# WIFI_0831.net
KiCad netlist of a schematic drawn in Altium Designer
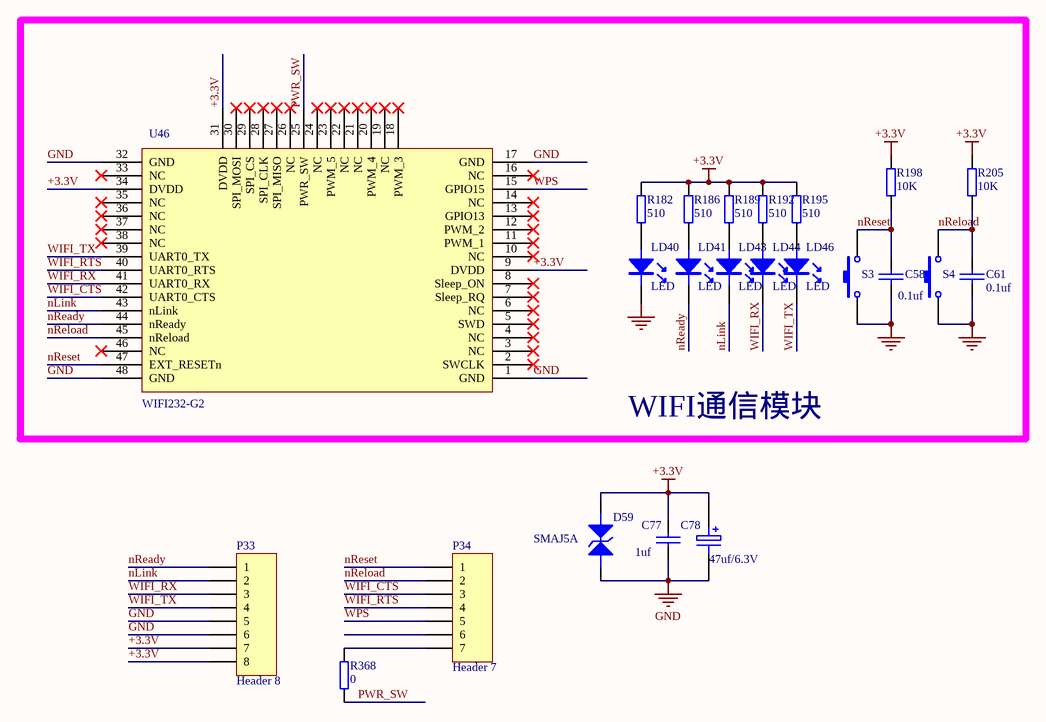
[diagram p0: 如意硬件WIFI模块0831.SchDoc]

(export (version "E")
  (design (tool "Eeschema 10.0.6"))
  (components
    (comp (ref "C58")
      (value "0.1uf")
      (footprint "0603C-1")
      (description "Capacitor")
      (libsource (lib "*") (part "CAP"))
    )
    (comp (ref "C61")
      (value "0.1uf")
      (footprint "0603C-1")
      (description "Capacitor")
      (libsource (lib "*") (part "CAP"))
    )
    (comp (ref "C77")
      (value "1uf")
      (footprint "0603C-1")
      (description "Capacitor")
      (libsource (lib "*") (part "CAP"))
    )
    (comp (ref "C78")
      (value "47uf/6.3V")
      (footprint "1206D-S")
      (description "Electrolytic Capacitor")
      (libsource (lib "*") (part "ELECTRO1"))
    )
    (comp (ref "D59") (value "SMAJ5A") (footprint "SMB") (libsource (lib "*") (part "TVS")))
    (comp (ref "LD40") (value "LED") (footprint "LED_Z1") (libsource (lib "*") (part "LED")))
    (comp (ref "LD41") (value "LED") (footprint "LED_Z1") (libsource (lib "*") (part "LED")))
    (comp (ref "LD43") (value "LED") (footprint "LED_Z1") (libsource (lib "*") (part "LED")))
    (comp (ref "LD44") (value "LED") (footprint "LED_Z1") (libsource (lib "*") (part "LED")))
    (comp (ref "LD46") (value "LED") (footprint "LED_Z1") (libsource (lib "*") (part "LED")))
    (comp (ref "P33")
      (value "Header 8")
      (footprint "HDR1X8")
      (description "Header, 8-Pin")
      (fields (field (name "PUBLISHER") "Altium Limited"))
      (libsource (lib "Miscellaneous Connectors") (part "Header 8"))
    )
    (comp (ref "P34")
      (value "Header 7")
      (footprint "HDR1X7")
      (description "Header, 7-Pin")
      (fields (field (name "PUBLISHER") "Altium Limited"))
      (libsource (lib "Miscellaneous Connectors") (part "Header 7"))
    )
    (comp (ref "R182") (value "510") (footprint "0603R-1") (libsource (lib "*") (part "RES-2")))
    (comp (ref "R186") (value "510") (footprint "0603R-1") (libsource (lib "*") (part "RES-2")))
    (comp (ref "R189") (value "510") (footprint "0603R-1") (libsource (lib "*") (part "RES-2")))
    (comp (ref "R192") (value "510") (footprint "0603R-1") (libsource (lib "*") (part "RES-2")))
    (comp (ref "R195") (value "510") (footprint "0603R-1") (libsource (lib "*") (part "RES-2")))
    (comp (ref "R198") (value "10K") (footprint "0603R-1") (libsource (lib "*") (part "RES-2")))
    (comp (ref "R205") (value "10K") (footprint "0603R-1") (libsource (lib "*") (part "RES-2")))
    (comp (ref "R368") (value "0") (footprint "0603R-1") (libsource (lib "*") (part "RES-2")))
    (comp (ref "S3")
      (value "SW-PB")
      (footprint "SW_PB4_A1")
      (description "Switch")
      (fields (field (name "PUBLISHER") "Altium Limited"))
      (libsource (lib "*") (part "SW-PB"))
    )
    (comp (ref "S4")
      (value "SW-PB")
      (footprint "SW_PB4_A1")
      (description "Switch")
      (fields (field (name "PUBLISHER") "Altium Limited"))
      (libsource (lib "*") (part "SW-PB"))
    )
    (comp (ref "U46")
      (value "WIFI232-G2")
      (footprint "USR-WIFI232-G2")
      (libsource (lib "zongruyi") (part "WIFI232-G2"))
    )
  )
  (nets
    (net (code "1") (name "+3.3V") (class "Default")
      (node (ref "C77") (pin "1") (pinfunction "1_1") (pintype "passive"))
      (node (ref "C78") (pin "1") (pinfunction "1_1") (pintype "passive"))
      (node (ref "D59") (pin "2") (pinfunction "K_2") (pintype "passive"))
      (node (ref "P33") (pin "7") (pinfunction "7_7") (pintype "passive"))
      (node (ref "P33") (pin "8") (pinfunction "8_8") (pintype "passive"))
      (node (ref "R182") (pin "1") (pinfunction "1_1") (pintype "passive"))
      (node (ref "R186") (pin "1") (pinfunction "1_1") (pintype "passive"))
      (node (ref "R189") (pin "1") (pinfunction "1_1") (pintype "passive"))
      (node (ref "R192") (pin "1") (pinfunction "1_1") (pintype "passive"))
      (node (ref "R195") (pin "1") (pinfunction "1_1") (pintype "passive"))
      (node (ref "R198") (pin "1") (pinfunction "1_1") (pintype "passive"))
      (node (ref "R205") (pin "1") (pinfunction "1_1") (pintype "passive"))
      (node (ref "U46") (pin "31") (pinfunction "DVDD_31") (pintype "passive"))
      (node (ref "U46") (pin "34") (pinfunction "DVDD_34") (pintype "passive"))
      (node (ref "U46") (pin "9") (pinfunction "DVDD_9") (pintype "passive"))
    )
    (net (code "2") (name "/PWR_SW") (class "Default")
      (node (ref "R368") (pin "2") (pinfunction "2_2") (pintype "passive"))
      (node (ref "U46") (pin "25") (pinfunction "PWR_SW_25") (pintype "passive"))
    )
    (net (code "3") (name "/WIFI_CTS") (class "Default")
      (node (ref "P34") (pin "3") (pinfunction "3_3") (pintype "passive"))
      (node (ref "U46") (pin "42") (pinfunction "UART0_CTS_42") (pintype "passive"))
    )
    (net (code "4") (name "/WIFI_RTS") (class "Default")
      (node (ref "P34") (pin "4") (pinfunction "4_4") (pintype "passive"))
      (node (ref "U46") (pin "40") (pinfunction "UART0_RTS_40") (pintype "passive"))
    )
    (net (code "5") (name "/WIFI_RX") (class "Default")
      (node (ref "LD44") (pin "2") (pinfunction "2_2") (pintype "passive"))
      (node (ref "P33") (pin "3") (pinfunction "3_3") (pintype "passive"))
      (node (ref "U46") (pin "41") (pinfunction "UART0_RX_41") (pintype "passive"))
    )
    (net (code "6") (name "/WIFI_TX") (class "Default")
      (node (ref "LD46") (pin "2") (pinfunction "2_2") (pintype "passive"))
      (node (ref "P33") (pin "4") (pinfunction "4_4") (pintype "passive"))
      (node (ref "U46") (pin "39") (pinfunction "UART0_TX_39") (pintype "passive"))
    )
    (net (code "7") (name "/WPS") (class "Default")
      (node (ref "P34") (pin "5") (pinfunction "5_5") (pintype "passive"))
      (node (ref "U46") (pin "15") (pinfunction "GPIO15_15") (pintype "passive"))
    )
    (net (code "8") (name "/nLink") (class "Default")
      (node (ref "LD43") (pin "2") (pinfunction "2_2") (pintype "passive"))
      (node (ref "P33") (pin "2") (pinfunction "2_2") (pintype "passive"))
      (node (ref "U46") (pin "43") (pinfunction "nLink_43") (pintype "passive"))
    )
    (net (code "9") (name "/nReady") (class "Default")
      (node (ref "LD41") (pin "2") (pinfunction "2_2") (pintype "passive"))
      (node (ref "P33") (pin "1") (pinfunction "1_1") (pintype "passive"))
      (node (ref "U46") (pin "44") (pinfunction "nReady_44") (pintype "passive"))
    )
    (net (code "10") (name "/nReload") (class "Default")
      (node (ref "C61") (pin "1") (pinfunction "1_1") (pintype "passive"))
      (node (ref "P34") (pin "2") (pinfunction "2_2") (pintype "passive"))
      (node (ref "R205") (pin "2") (pinfunction "2_2") (pintype "passive"))
      (node (ref "S4") (pin "2") (pinfunction "2_2") (pintype "passive"))
      (node (ref "U46") (pin "45") (pinfunction "nReload_45") (pintype "passive"))
    )
    (net (code "11") (name "/nReset") (class "Default")
      (node (ref "C58") (pin "1") (pinfunction "1_1") (pintype "passive"))
      (node (ref "P34") (pin "1") (pinfunction "1_1") (pintype "passive"))
      (node (ref "R198") (pin "2") (pinfunction "2_2") (pintype "passive"))
      (node (ref "S3") (pin "2") (pinfunction "2_2") (pintype "passive"))
      (node (ref "U46") (pin "47") (pinfunction "EXT_RESETn_47") (pintype "passive"))
    )
    (net (code "12") (name "GND") (class "Default")
      (node (ref "C58") (pin "2") (pinfunction "2_2") (pintype "passive"))
      (node (ref "C61") (pin "2") (pinfunction "2_2") (pintype "passive"))
      (node (ref "C77") (pin "2") (pinfunction "2_2") (pintype "passive"))
      (node (ref "C78") (pin "2") (pinfunction "2_2") (pintype "passive"))
      (node (ref "D59") (pin "1") (pinfunction "A_1") (pintype "passive"))
      (node (ref "LD40") (pin "2") (pinfunction "2_2") (pintype "passive"))
      (node (ref "P33") (pin "5") (pinfunction "5_5") (pintype "passive"))
      (node (ref "P33") (pin "6") (pinfunction "6_6") (pintype "passive"))
      (node (ref "S3") (pin "1") (pinfunction "1_1") (pintype "passive"))
      (node (ref "S4") (pin "1") (pinfunction "1_1") (pintype "passive"))
      (node (ref "U46") (pin "1") (pinfunction "GND_1") (pintype "passive"))
      (node (ref "U46") (pin "17") (pinfunction "GND_17") (pintype "passive"))
      (node (ref "U46") (pin "32") (pinfunction "GND_32") (pintype "passive"))
      (node (ref "U46") (pin "48") (pinfunction "GND_48") (pintype "passive"))
    )
    (net (code "13") (name "Net-(LD40-Pad1)") (class "Default")
      (node (ref "LD40") (pin "1") (pinfunction "1_1") (pintype "passive"))
      (node (ref "R182") (pin "2") (pinfunction "2_2") (pintype "passive"))
    )
    (net (code "14") (name "Net-(LD41-Pad1)") (class "Default")
      (node (ref "LD41") (pin "1") (pinfunction "1_1") (pintype "passive"))
      (node (ref "R186") (pin "2") (pinfunction "2_2") (pintype "passive"))
    )
    (net (code "15") (name "Net-(LD43-Pad1)") (class "Default")
      (node (ref "LD43") (pin "1") (pinfunction "1_1") (pintype "passive"))
      (node (ref "R189") (pin "2") (pinfunction "2_2") (pintype "passive"))
    )
    (net (code "16") (name "Net-(LD44-Pad1)") (class "Default")
      (node (ref "LD44") (pin "1") (pinfunction "1_1") (pintype "passive"))
      (node (ref "R192") (pin "2") (pinfunction "2_2") (pintype "passive"))
    )
    (net (code "17") (name "Net-(LD46-Pad1)") (class "Default")
      (node (ref "LD46") (pin "1") (pinfunction "1_1") (pintype "passive"))
      (node (ref "R195") (pin "2") (pinfunction "2_2") (pintype "passive"))
    )
    (net (code "18") (name "Net-(P34-Pad7)") (class "Default")
      (node (ref "P34") (pin "7") (pinfunction "7_7") (pintype "passive"))
      (node (ref "R368") (pin "1") (pinfunction "1_1") (pintype "passive"))
    )
    (net (code "19") (name "unconnected-(P34-Pad6)") (class "Default")
      (node (ref "P34") (pin "6") (pinfunction "6_6") (pintype "passive"))
    )
    (net (code "20") (name "unconnected-(U46-GPIO13-Pad13)") (class "Default")
      (node (ref "U46") (pin "13") (pinfunction "GPIO13_13") (pintype "passive+no_connect"))
    )
    (net (code "21") (name "unconnected-(U46-NC-Pad3)") (class "Default")
      (node (ref "U46") (pin "3") (pinfunction "NC_3") (pintype "passive+no_connect"))
    )
    (net (code "22") (name "unconnected-(U46-NC-Pad4)") (class "Default")
      (node (ref "U46") (pin "4") (pinfunction "NC_4") (pintype "passive+no_connect"))
    )
    (net (code "23") (name "unconnected-(U46-NC-Pad6)") (class "Default")
      (node (ref "U46") (pin "6") (pinfunction "NC_6") (pintype "passive+no_connect"))
    )
    (net (code "24") (name "unconnected-(U46-NC-Pad10)") (class "Default")
      (node (ref "U46") (pin "10") (pinfunction "NC_10") (pintype "passive+no_connect"))
    )
    (net (code "25") (name "unconnected-(U46-NC-Pad14)") (class "Default")
      (node (ref "U46") (pin "14") (pinfunction "NC_14") (pintype "passive+no_connect"))
    )
    (net (code "26") (name "unconnected-(U46-NC-Pad16)") (class "Default")
      (node (ref "U46") (pin "16") (pinfunction "NC_16") (pintype "passive+no_connect"))
    )
    (net (code "27") (name "unconnected-(U46-NC-Pad19)") (class "Default")
      (node (ref "U46") (pin "19") (pinfunction "NC_19") (pintype "passive+no_connect"))
    )
    (net (code "28") (name "unconnected-(U46-NC-Pad21)") (class "Default")
      (node (ref "U46") (pin "21") (pinfunction "NC_21") (pintype "passive+no_connect"))
    )
    (net (code "29") (name "unconnected-(U46-NC-Pad22)") (class "Default")
      (node (ref "U46") (pin "22") (pinfunction "NC_22") (pintype "passive+no_connect"))
    )
    (net (code "30") (name "unconnected-(U46-NC-Pad24)") (class "Default")
      (node (ref "U46") (pin "24") (pinfunction "NC_24") (pintype "passive+no_connect"))
    )
    (net (code "31") (name "unconnected-(U46-NC-Pad26)") (class "Default")
      (node (ref "U46") (pin "26") (pinfunction "NC_26") (pintype "passive+no_connect"))
    )
    (net (code "32") (name "unconnected-(U46-NC-Pad33)") (class "Default")
      (node (ref "U46") (pin "33") (pinfunction "NC_33") (pintype "passive+no_connect"))
    )
    (net (code "33") (name "unconnected-(U46-NC-Pad35)") (class "Default")
      (node (ref "U46") (pin "35") (pinfunction "NC_35") (pintype "passive+no_connect"))
    )
    (net (code "34") (name "unconnected-(U46-NC-Pad36)") (class "Default")
      (node (ref "U46") (pin "36") (pinfunction "NC_36") (pintype "passive+no_connect"))
    )
    (net (code "35") (name "unconnected-(U46-NC-Pad37)") (class "Default")
      (node (ref "U46") (pin "37") (pinfunction "NC_37") (pintype "passive+no_connect"))
    )
    (net (code "36") (name "unconnected-(U46-NC-Pad38)") (class "Default")
      (node (ref "U46") (pin "38") (pinfunction "NC_38") (pintype "passive+no_connect"))
    )
    (net (code "37") (name "unconnected-(U46-NC-Pad46)") (class "Default")
      (node (ref "U46") (pin "46") (pinfunction "NC_46") (pintype "passive+no_connect"))
    )
    (net (code "38") (name "unconnected-(U46-PWM_1-Pad11)") (class "Default")
      (node (ref "U46") (pin "11") (pinfunction "PWM_1_11") (pintype "passive+no_connect"))
    )
    (net (code "39") (name "unconnected-(U46-PWM_2-Pad12)") (class "Default")
      (node (ref "U46") (pin "12") (pinfunction "PWM_2_12") (pintype "passive+no_connect"))
    )
    (net (code "40") (name "unconnected-(U46-PWM_3-Pad18)") (class "Default")
      (node (ref "U46") (pin "18") (pinfunction "PWM_3_18") (pintype "passive+no_connect"))
    )
    (net (code "41") (name "unconnected-(U46-PWM_4-Pad20)") (class "Default")
      (node (ref "U46") (pin "20") (pinfunction "PWM_4_20") (pintype "passive+no_connect"))
    )
    (net (code "42") (name "unconnected-(U46-PWM_5-Pad23)") (class "Default")
      (node (ref "U46") (pin "23") (pinfunction "PWM_5_23") (pintype "passive+no_connect"))
    )
    (net (code "43") (name "unconnected-(U46-SPI_CLK-Pad28)") (class "Default")
      (node (ref "U46") (pin "28") (pinfunction "SPI_CLK_28") (pintype "passive+no_connect"))
    )
    (net (code "44") (name "unconnected-(U46-SPI_CS-Pad29)") (class "Default")
      (node (ref "U46") (pin "29") (pinfunction "SPI_CS_29") (pintype "passive+no_connect"))
    )
    (net (code "45") (name "unconnected-(U46-SPI_MISO-Pad27)") (class "Default")
      (node (ref "U46") (pin "27") (pinfunction "SPI_MISO_27") (pintype "passive+no_connect"))
    )
    (net (code "46") (name "unconnected-(U46-SPI_MOSI-Pad30)") (class "Default")
      (node (ref "U46") (pin "30") (pinfunction "SPI_MOSI_30") (pintype "passive+no_connect"))
    )
    (net (code "47") (name "unconnected-(U46-SWCLK-Pad2)") (class "Default")
      (node (ref "U46") (pin "2") (pinfunction "SWCLK_2") (pintype "passive+no_connect"))
    )
    (net (code "48") (name "unconnected-(U46-SWD-Pad5)") (class "Default")
      (node (ref "U46") (pin "5") (pinfunction "SWD_5") (pintype "passive+no_connect"))
    )
    (net (code "49") (name "unconnected-(U46-Sleep_ON-Pad8)") (class "Default")
      (node (ref "U46") (pin "8") (pinfunction "Sleep_ON_8") (pintype "passive+no_connect"))
    )
    (net (code "50") (name "unconnected-(U46-Sleep_RQ-Pad7)") (class "Default")
      (node (ref "U46") (pin "7") (pinfunction "Sleep_RQ_7") (pintype "passive+no_connect"))
    )
  )
)
